# 6coils-1.net
KiCad netlist of a schematic drawn in EasyEDA
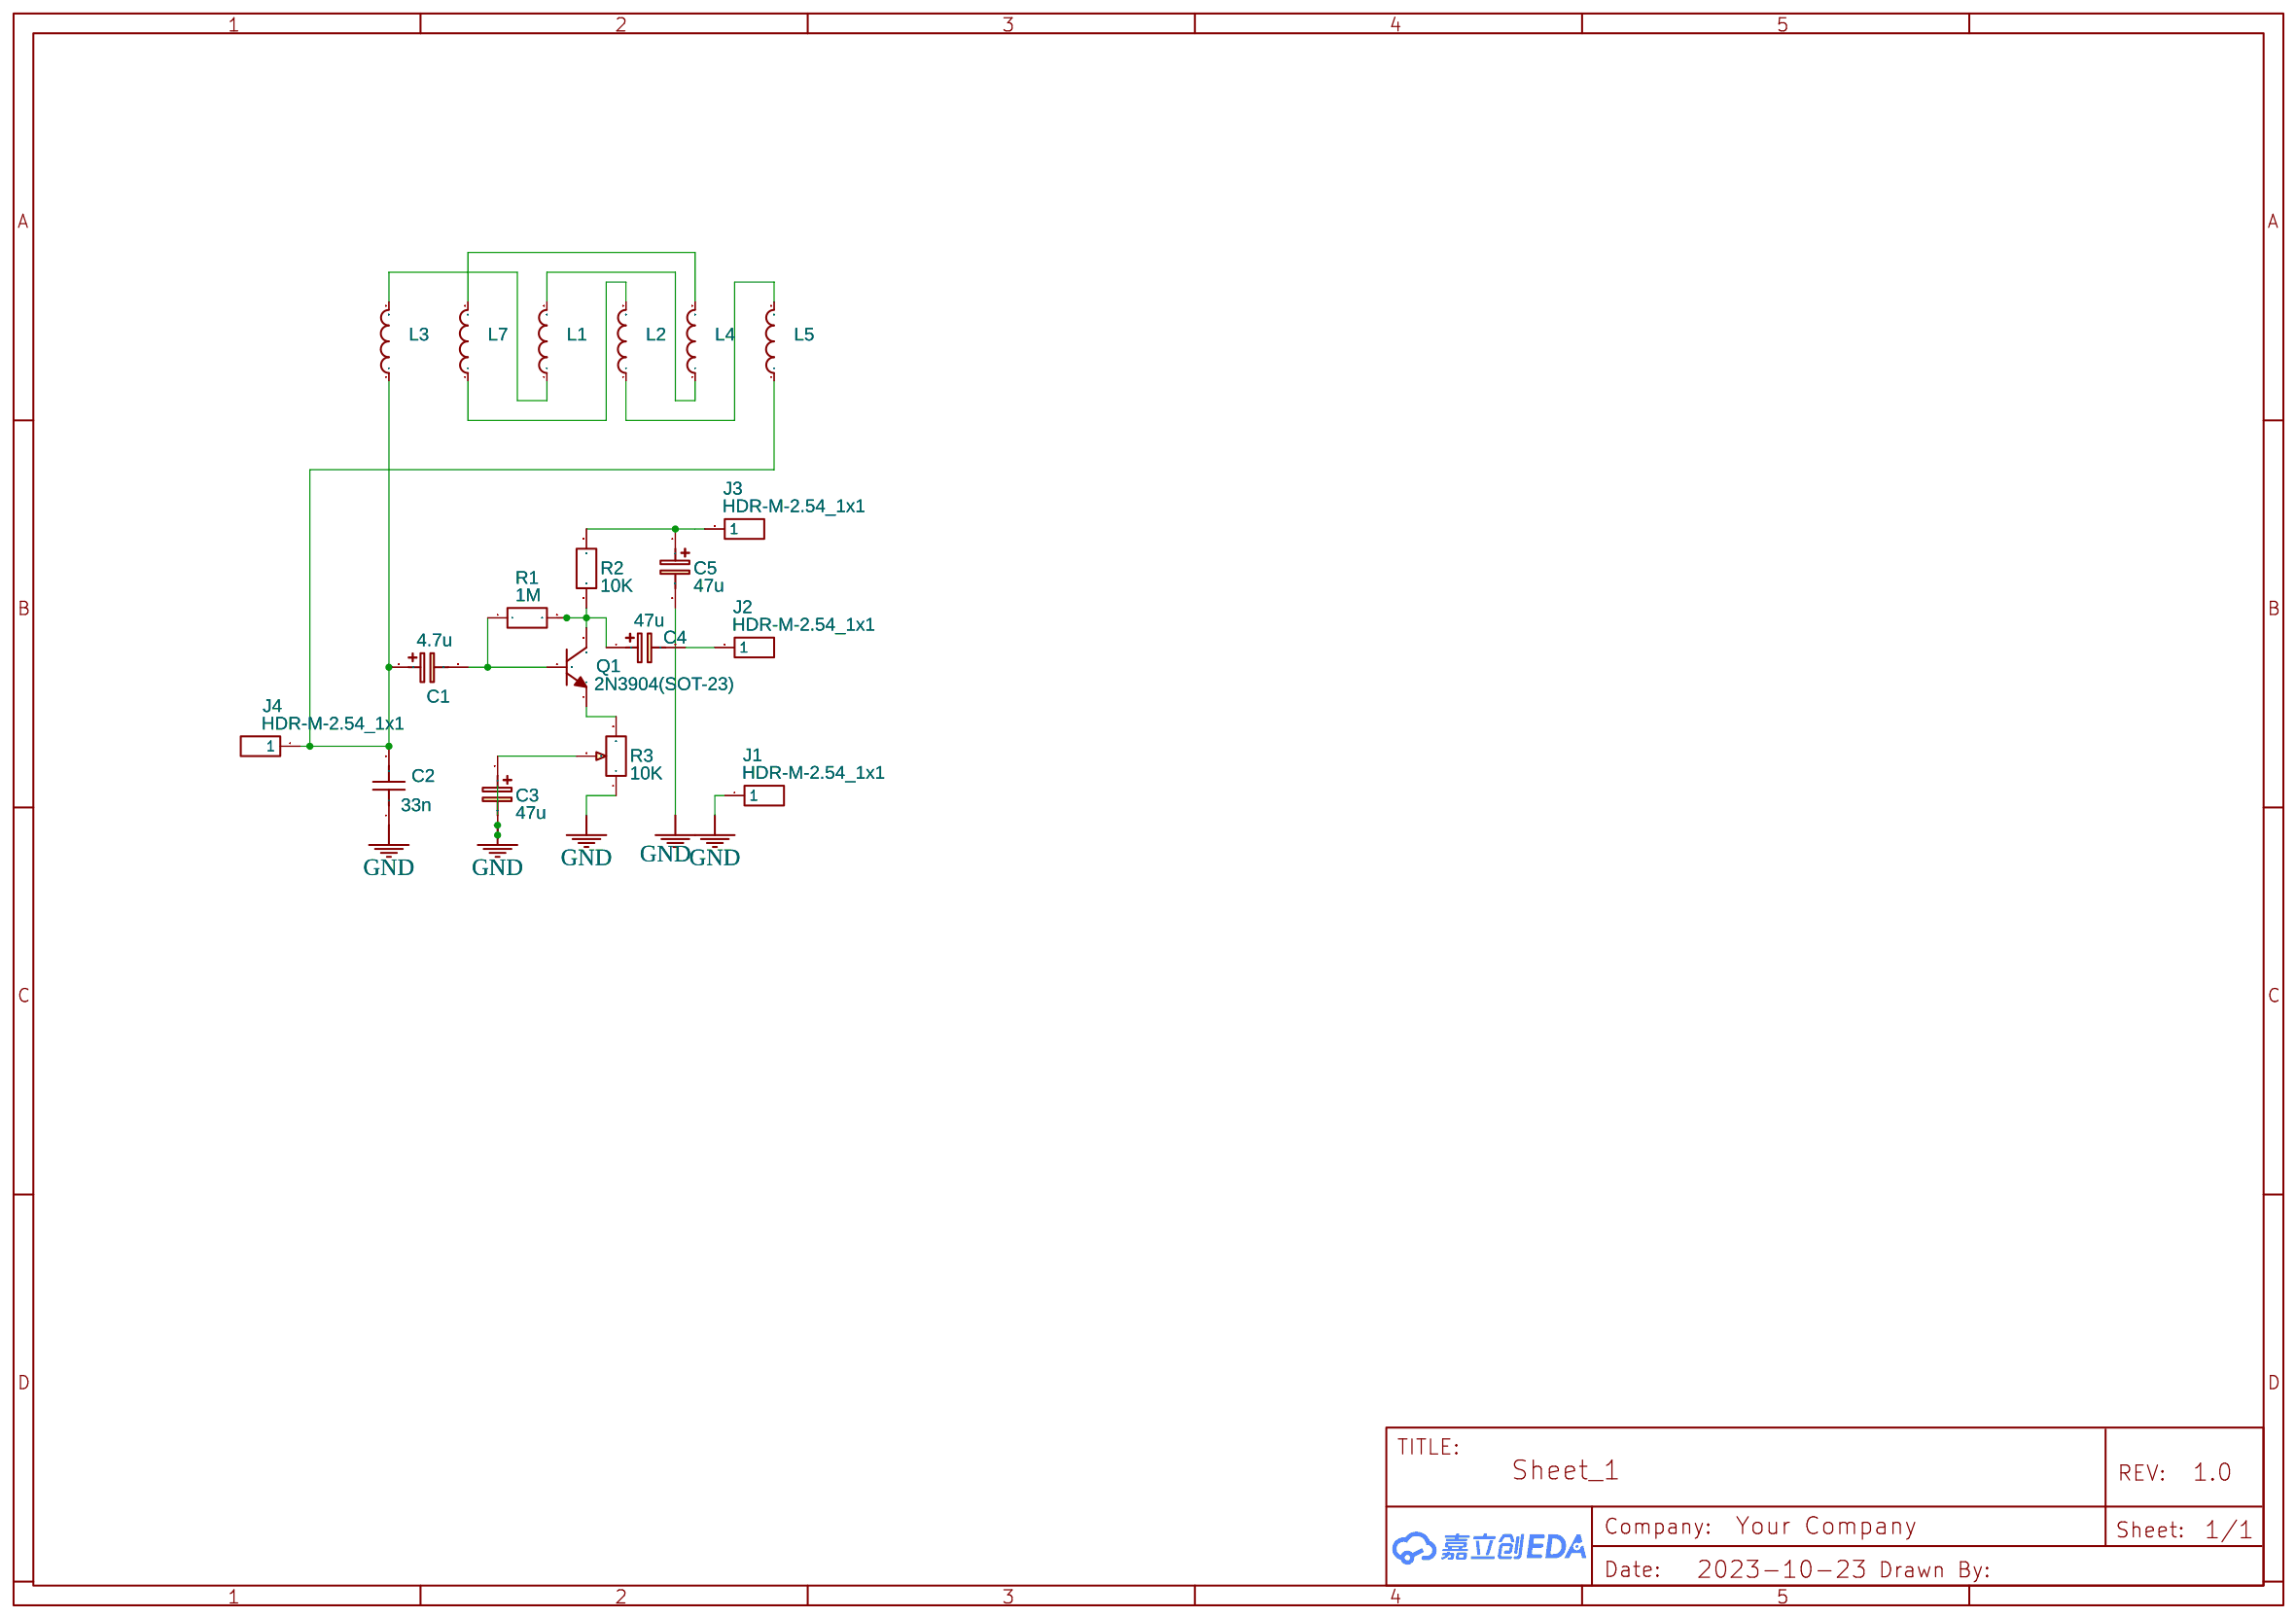
[diagram p0: schematic sheet]

(export (version "E")
  (design (tool "Eeschema 10.0.6"))
  (components
    (comp (ref "C1") (value "4.7u") (libsource (lib "") (part "C_Tan_SMD_A_EU_1")))
    (comp (ref "C2") (value "33n") (libsource (lib "") (part "C_0603_US")))
    (comp (ref "C3") (value "47u") (libsource (lib "") (part "C_Tan_SMD_A_EU_3")))
    (comp (ref "C4") (value "47u") (libsource (lib "") (part "C_Tan_SMD_A_EU_2")))
    (comp (ref "C5") (value "47u") (libsource (lib "") (part "C_Tan_SMD_A_EU")))
    (comp (ref "J1")
      (value "HDR-M-2.54_1x1")
      (fields (field (name "BOM_Supplier Part") "C81276"))
      (libsource (lib "") (part "HDR-M-2.54_1x1"))
    )
    (comp (ref "J2")
      (value "HDR-M-2.54_1x1")
      (fields (field (name "BOM_Supplier Part") "C81276"))
      (libsource (lib "") (part "HDR-M-2.54_1x1"))
    )
    (comp (ref "J3")
      (value "HDR-M-2.54_1x1")
      (fields (field (name "BOM_Supplier Part") "C81276"))
      (libsource (lib "") (part "HDR-M-2.54_1x1"))
    )
    (comp (ref "J4")
      (value "HDR-M-2.54_1x1")
      (fields (field (name "BOM_Supplier Part") "C81276"))
      (libsource (lib "") (part "HDR-M-2.54_1x1_1"))
    )
    (comp (ref "L1")
      (value "INDUCTOR_SMD:L_COILCRAFT_XXL4040")
      (fields (field (name "Manufacturer Part") "Inductor_SMD:L_Coilcraft_XxL4040"))
      (libsource (lib "") (part "INDUCTOR_SMD{colon}L_COILCRAFT_XXL4040"))
    )
    (comp (ref "L2")
      (value "INDUCTOR_SMD:L_COILCRAFT_XXL4040")
      (fields (field (name "Manufacturer Part") "Inductor_SMD:L_Coilcraft_XxL4040"))
      (libsource (lib "") (part "INDUCTOR_SMD{colon}L_COILCRAFT_XXL4040"))
    )
    (comp (ref "L3")
      (value "INDUCTOR_SMD:L_COILCRAFT_XXL4040")
      (fields (field (name "Manufacturer Part") "Inductor_SMD:L_Coilcraft_XxL4040"))
      (libsource (lib "") (part "INDUCTOR_SMD{colon}L_COILCRAFT_XXL4040_1"))
    )
    (comp (ref "L4")
      (value "INDUCTOR_SMD:L_COILCRAFT_XXL4040")
      (fields (field (name "Manufacturer Part") "Inductor_SMD:L_Coilcraft_XxL4040"))
      (libsource (lib "") (part "INDUCTOR_SMD{colon}L_COILCRAFT_XXL4040"))
    )
    (comp (ref "L5")
      (value "INDUCTOR_SMD:L_COILCRAFT_XXL4040")
      (fields (field (name "Manufacturer Part") "Inductor_SMD:L_Coilcraft_XxL4040"))
      (libsource (lib "") (part "INDUCTOR_SMD{colon}L_COILCRAFT_XXL4040"))
    )
    (comp (ref "L7")
      (value "INDUCTOR_SMD:L_COILCRAFT_XXL4040")
      (fields (field (name "Manufacturer Part") "Inductor_SMD:L_Coilcraft_XxL4040"))
      (libsource (lib "") (part "INDUCTOR_SMD{colon}L_COILCRAFT_XXL4040_1"))
    )
    (comp (ref "Q1")
      (value "2N3904(SOT-23)")
      (fields
        (field (name "BOM_Manufacturer Part") "2n3904S-RTK/PS")
        (field (name "BOM_Supplier Part") "C18536")
      )
      (libsource (lib "") (part "2N3904(SOT-23)"))
    )
    (comp (ref "R1") (value "1M") (libsource (lib "") (part "R_0603_EU")))
    (comp (ref "R2") (value "10K") (libsource (lib "") (part "R_0603_EU_1")))
    (comp (ref "R3")
      (value "10K")
      (fields (field (name "Manufacturer Part") "RM063-103 10K") (field (name "Manufacturer") "JML"))
      (libsource (lib "") (part "RM063-103 10K"))
    )
  )
  (nets
    (net (code "1") (name "GND") (class "Default")
      (node (ref "C2") (pin "1") (pinfunction "1_1") (pintype "unspecified"))
      (node (ref "C3") (pin "2") (pinfunction "2_2") (pintype "unspecified"))
      (node (ref "C5") (pin "2") (pinfunction "2_2") (pintype "unspecified"))
      (node (ref "J1") (pin "1") (pinfunction "1_1") (pintype "input"))
      (node (ref "R3") (pin "1") (pinfunction "1_1") (pintype "input"))
    )
    (net (code "2") (name "Net-(C1-Pad1)") (class "Default")
      (node (ref "C1") (pin "1") (pinfunction "1_1") (pintype "unspecified"))
      (node (ref "C2") (pin "2") (pinfunction "2_2") (pintype "unspecified"))
      (node (ref "J4") (pin "1") (pinfunction "1_1") (pintype "input"))
      (node (ref "L3") (pin "1") (pinfunction "1_1") (pintype "unspecified"))
      (node (ref "L5") (pin "1") (pinfunction "1_1") (pintype "unspecified"))
    )
    (net (code "3") (name "Net-(C3-Pad1)") (class "Default")
      (node (ref "C3") (pin "1") (pinfunction "1_1") (pintype "unspecified"))
      (node (ref "R3") (pin "2") (pinfunction "2_2") (pintype "input"))
    )
    (net (code "4") (name "Net-(C4-Pad2)") (class "Default")
      (node (ref "C4") (pin "2") (pinfunction "2_2") (pintype "unspecified"))
      (node (ref "J2") (pin "1") (pinfunction "1_1") (pintype "input"))
    )
    (net (code "5") (name "Net-(C5-Pad1)") (class "Default")
      (node (ref "C5") (pin "1") (pinfunction "1_1") (pintype "unspecified"))
      (node (ref "J3") (pin "1") (pinfunction "1_1") (pintype "input"))
      (node (ref "R2") (pin "2") (pinfunction "2_2") (pintype "unspecified"))
    )
    (net (code "6") (name "Net-(L1-Pad1)") (class "Default")
      (node (ref "L1") (pin "1") (pinfunction "1_1") (pintype "unspecified"))
      (node (ref "L3") (pin "2") (pinfunction "2_2") (pintype "unspecified"))
    )
    (net (code "7") (name "Net-(L1-Pad2)") (class "Default")
      (node (ref "L1") (pin "2") (pinfunction "2_2") (pintype "unspecified"))
      (node (ref "L4") (pin "1") (pinfunction "1_1") (pintype "unspecified"))
    )
    (net (code "8") (name "Net-(L2-Pad1)") (class "Default")
      (node (ref "L2") (pin "1") (pinfunction "1_1") (pintype "unspecified"))
      (node (ref "L5") (pin "2") (pinfunction "2_2") (pintype "unspecified"))
    )
    (net (code "9") (name "Net-(L2-Pad2)") (class "Default")
      (node (ref "L2") (pin "2") (pinfunction "2_2") (pintype "unspecified"))
      (node (ref "L7") (pin "1") (pinfunction "1_1") (pintype "unspecified"))
    )
    (net (code "10") (name "Net-(L4-Pad2)") (class "Default")
      (node (ref "L4") (pin "2") (pinfunction "2_2") (pintype "unspecified"))
      (node (ref "L7") (pin "2") (pinfunction "2_2") (pintype "unspecified"))
    )
    (net (code "11") (name "Net-(Q1-B)") (class "Default")
      (node (ref "C1") (pin "2") (pinfunction "2_2") (pintype "unspecified"))
      (node (ref "Q1") (pin "2") (pinfunction "B_2") (pintype "input"))
      (node (ref "R1") (pin "1") (pinfunction "1_1") (pintype "unspecified"))
    )
    (net (code "12") (name "Net-(Q1-C)") (class "Default")
      (node (ref "C4") (pin "1") (pinfunction "1_1") (pintype "unspecified"))
      (node (ref "Q1") (pin "3") (pinfunction "C_3") (pintype "input"))
      (node (ref "R1") (pin "2") (pinfunction "2_2") (pintype "unspecified"))
      (node (ref "R2") (pin "1") (pinfunction "1_1") (pintype "unspecified"))
    )
    (net (code "13") (name "Net-(Q1-E)") (class "Default")
      (node (ref "Q1") (pin "1") (pinfunction "E_1") (pintype "input"))
      (node (ref "R3") (pin "3") (pinfunction "3_3") (pintype "input"))
    )
  )
)
